# AT90PWM_PCB.net
KiCad netlist of a schematic drawn in Altium Designer
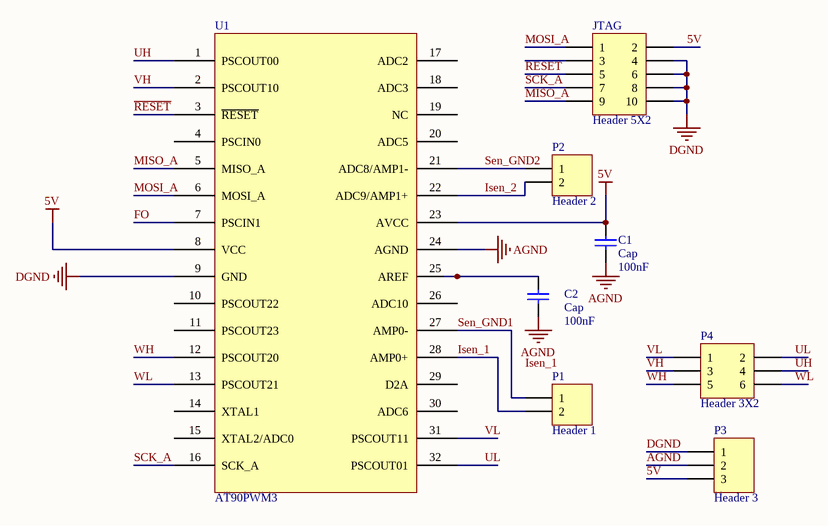
[diagram p0: AT90PWM_PCB.SchDoc]

(export (version "E")
  (design (tool "Eeschema 10.0.6"))
  (components
    (comp (ref "C1")
      (value "Cap")
      (footprint "NPolar_Cap")
      (description "Capacitor")
      (fields (field (name "ALTIUM_VALUE") "100nF") (field (name "PUBLISHER") "Altium Limited"))
      (libsource (lib "Miscellaneous Devices") (part "Cap"))
    )
    (comp (ref "C2")
      (value "Cap")
      (footprint "NPolar_Cap")
      (description "Capacitor")
      (fields (field (name "ALTIUM_VALUE") "100nF") (field (name "PUBLISHER") "Altium Limited"))
      (libsource (lib "Miscellaneous Devices") (part "Cap"))
    )
    (comp (ref "JTAG")
      (value "Header 5X2")
      (footprint "HDR2X5")
      (description "Header, 5-Pin, Dual row")
      (fields (field (name "PUBLISHER") "Altium Limited"))
      (libsource (lib "Miscellaneous Connectors") (part "Header 5X2"))
    )
    (comp (ref "P1")
      (value "Header 1")
      (footprint "HDR1X2")
      (description "Header, 2-Pin")
      (fields (field (name "PUBLISHER") "Altium Limited"))
      (libsource (lib "Miscellaneous Connectors") (part "Header 2"))
    )
    (comp (ref "P2")
      (value "Header 2")
      (footprint "HDR1X2")
      (description "Header, 2-Pin")
      (fields (field (name "PUBLISHER") "Altium Limited"))
      (libsource (lib "Miscellaneous Connectors") (part "Header 2"))
    )
    (comp (ref "P3")
      (value "Header 3")
      (footprint "HDR1X3")
      (description "Header, 3-Pin")
      (fields (field (name "PUBLISHER") "Altium Limited"))
      (libsource (lib "Miscellaneous Connectors") (part "Header 3"))
    )
    (comp (ref "P4")
      (value "Header 3X2")
      (footprint "HDR2X3")
      (description "Header, 3-Pin, Dual row")
      (fields (field (name "PUBLISHER") "Altium Limited"))
      (libsource (lib "Miscellaneous Connectors") (part "Header 3X2"))
    )
    (comp (ref "U1")
      (value "AT90PWM3")
      (footprint "FYP:AT90PWM3B")
      (libsource (lib "MyBoard_v1") (part "AT90PWM3"))
    )
  )
  (nets
    (net (code "1") (name "/FO") (class "Default")
      (node (ref "U1") (pin "7") (pinfunction "PSCIN1_7") (pintype "passive"))
    )
    (net (code "2") (name "/Isen_1") (class "Default")
      (node (ref "P1") (pin "2") (pinfunction "2_2") (pintype "passive"))
      (node (ref "U1") (pin "28") (pinfunction "AMP0+_28") (pintype "passive"))
    )
    (net (code "3") (name "/Isen_2") (class "Default")
      (node (ref "P2") (pin "2") (pinfunction "2_2") (pintype "passive"))
      (node (ref "U1") (pin "22") (pinfunction "ADC9/AMP1+_22") (pintype "passive"))
    )
    (net (code "4") (name "/MISO_A") (class "Default")
      (node (ref "JTAG") (pin "9") (pinfunction "9_9") (pintype "passive"))
      (node (ref "U1") (pin "5") (pinfunction "MISO_A_5") (pintype "passive"))
    )
    (net (code "5") (name "/MOSI_A") (class "Default")
      (node (ref "JTAG") (pin "1") (pinfunction "1_1") (pintype "passive"))
      (node (ref "U1") (pin "6") (pinfunction "MOSI_A_6") (pintype "passive"))
    )
    (net (code "6") (name "/SCK_A") (class "Default")
      (node (ref "JTAG") (pin "7") (pinfunction "7_7") (pintype "passive"))
      (node (ref "U1") (pin "16") (pinfunction "SCK_A_16") (pintype "passive"))
    )
    (net (code "7") (name "/Sen_GND1") (class "Default")
      (node (ref "P1") (pin "1") (pinfunction "1_1") (pintype "passive"))
      (node (ref "U1") (pin "27") (pinfunction "AMP0-_27") (pintype "passive"))
    )
    (net (code "8") (name "/Sen_GND2") (class "Default")
      (node (ref "P2") (pin "1") (pinfunction "1_1") (pintype "passive"))
      (node (ref "U1") (pin "21") (pinfunction "ADC8/AMP1-_21") (pintype "passive"))
    )
    (net (code "9") (name "/UH") (class "Default")
      (node (ref "P4") (pin "4") (pinfunction "4_4") (pintype "passive"))
      (node (ref "U1") (pin "1") (pinfunction "PSCOUT00_1") (pintype "passive"))
    )
    (net (code "10") (name "/UL") (class "Default")
      (node (ref "P4") (pin "2") (pinfunction "2_2") (pintype "passive"))
      (node (ref "U1") (pin "32") (pinfunction "PSCOUT01_32") (pintype "passive"))
    )
    (net (code "11") (name "/VH") (class "Default")
      (node (ref "P4") (pin "3") (pinfunction "3_3") (pintype "passive"))
      (node (ref "U1") (pin "2") (pinfunction "PSCOUT10_2") (pintype "passive"))
    )
    (net (code "12") (name "/VL") (class "Default")
      (node (ref "P4") (pin "1") (pinfunction "1_1") (pintype "passive"))
      (node (ref "U1") (pin "31") (pinfunction "PSCOUT11_31") (pintype "passive"))
    )
    (net (code "13") (name "/WH") (class "Default")
      (node (ref "P4") (pin "5") (pinfunction "5_5") (pintype "passive"))
      (node (ref "U1") (pin "12") (pinfunction "PSCOUT20_12") (pintype "passive"))
    )
    (net (code "14") (name "/WL") (class "Default")
      (node (ref "P4") (pin "6") (pinfunction "6_6") (pintype "passive"))
      (node (ref "U1") (pin "13") (pinfunction "PSCOUT21_13") (pintype "passive"))
    )
    (net (code "15") (name "/~{RESET}") (class "Default")
      (node (ref "JTAG") (pin "5") (pinfunction "5_5") (pintype "passive"))
      (node (ref "U1") (pin "3") (pinfunction "~{RESET}_3") (pintype "passive"))
    )
    (net (code "16") (name "5V") (class "Default")
      (node (ref "C1") (pin "2") (pinfunction "2_2") (pintype "passive"))
      (node (ref "JTAG") (pin "2") (pinfunction "2_2") (pintype "passive"))
      (node (ref "P3") (pin "3") (pinfunction "3_3") (pintype "passive"))
      (node (ref "U1") (pin "23") (pinfunction "AVCC_23") (pintype "passive"))
      (node (ref "U1") (pin "8") (pinfunction "VCC_8") (pintype "passive"))
    )
    (net (code "17") (name "AGND") (class "Default")
      (node (ref "C1") (pin "1") (pinfunction "1_1") (pintype "passive"))
      (node (ref "C2") (pin "1") (pinfunction "1_1") (pintype "passive"))
      (node (ref "P3") (pin "2") (pinfunction "2_2") (pintype "passive"))
      (node (ref "U1") (pin "24") (pinfunction "AGND_24") (pintype "passive"))
    )
    (net (code "18") (name "DGND") (class "Default")
      (node (ref "JTAG") (pin "10") (pinfunction "10_10") (pintype "passive"))
      (node (ref "JTAG") (pin "4") (pinfunction "4_4") (pintype "passive"))
      (node (ref "JTAG") (pin "6") (pinfunction "6_6") (pintype "passive"))
      (node (ref "JTAG") (pin "8") (pinfunction "8_8") (pintype "passive"))
      (node (ref "P3") (pin "1") (pinfunction "1_1") (pintype "passive"))
      (node (ref "U1") (pin "9") (pinfunction "GND_9") (pintype "passive"))
    )
    (net (code "19") (name "Net-(U1-AREF)") (class "Default")
      (node (ref "C2") (pin "2") (pinfunction "2_2") (pintype "passive"))
      (node (ref "U1") (pin "25") (pinfunction "AREF_25") (pintype "passive"))
    )
    (net (code "20") (name "unconnected-(JTAG-Pad3)") (class "Default")
      (node (ref "JTAG") (pin "3") (pinfunction "3_3") (pintype "passive"))
    )
    (net (code "21") (name "unconnected-(U1-ADC2-Pad17)") (class "Default")
      (node (ref "U1") (pin "17") (pinfunction "ADC2_17") (pintype "passive"))
    )
    (net (code "22") (name "unconnected-(U1-ADC3-Pad18)") (class "Default")
      (node (ref "U1") (pin "18") (pinfunction "ADC3_18") (pintype "passive"))
    )
    (net (code "23") (name "unconnected-(U1-ADC5-Pad20)") (class "Default")
      (node (ref "U1") (pin "20") (pinfunction "ADC5_20") (pintype "passive"))
    )
    (net (code "24") (name "unconnected-(U1-ADC6-Pad30)") (class "Default")
      (node (ref "U1") (pin "30") (pinfunction "ADC6_30") (pintype "passive"))
    )
    (net (code "25") (name "unconnected-(U1-ADC10-Pad26)") (class "Default")
      (node (ref "U1") (pin "26") (pinfunction "ADC10_26") (pintype "passive"))
    )
    (net (code "26") (name "unconnected-(U1-D2A-Pad29)") (class "Default")
      (node (ref "U1") (pin "29") (pinfunction "D2A_29") (pintype "passive"))
    )
    (net (code "27") (name "unconnected-(U1-NC-Pad19)") (class "Default")
      (node (ref "U1") (pin "19") (pinfunction "NC_19") (pintype "passive"))
    )
    (net (code "28") (name "unconnected-(U1-PSCIN0-Pad4)") (class "Default")
      (node (ref "U1") (pin "4") (pinfunction "PSCIN0_4") (pintype "passive"))
    )
    (net (code "29") (name "unconnected-(U1-PSCOUT22-Pad10)") (class "Default")
      (node (ref "U1") (pin "10") (pinfunction "PSCOUT22_10") (pintype "passive"))
    )
    (net (code "30") (name "unconnected-(U1-PSCOUT23-Pad11)") (class "Default")
      (node (ref "U1") (pin "11") (pinfunction "PSCOUT23_11") (pintype "passive"))
    )
    (net (code "31") (name "unconnected-(U1-XTAL1-Pad14)") (class "Default")
      (node (ref "U1") (pin "14") (pinfunction "XTAL1_14") (pintype "passive"))
    )
    (net (code "32") (name "unconnected-(U1-XTAL2{slash}ADC0-Pad15)") (class "Default")
      (node (ref "U1") (pin "15") (pinfunction "XTAL2/ADC0_15") (pintype "passive"))
    )
  )
)
